# sht21-breakout_v2.net
KiCad netlist of a schematic drawn in EAGLE
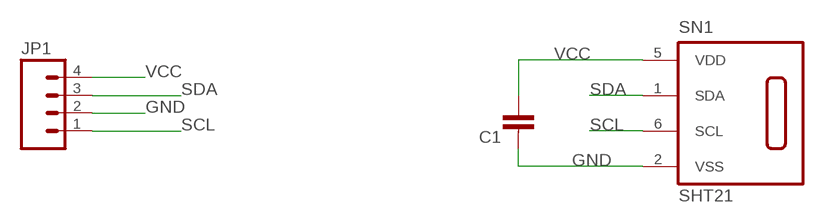
[diagram p0: schematic, sheet 1]

(export (version "E")
  (design (tool "Eeschema 10.0.6"))
  (components
    (comp (ref "C1")
      (value "CAPACITOR0603-N")
      (footprint "eagle-import:C0603-N")
      (libsource (lib "eagle-import") (part "CAPACITOR0603-N"))
    )
    (comp (ref "JP1")
      (value "M04LONGPADS")
      (footprint "eagle-import:1X04_LONGPADS")
      (libsource (lib "eagle-import") (part "M04LONGPADS"))
    )
    (comp (ref "SN1")
      (value "SHT21")
      (footprint "eagle-import:DFN6_SHT")
      (libsource (lib "eagle-import") (part "SHT21"))
    )
  )
  (nets
    (net (code "1") (name "/GND") (class "Default")
      (node (ref "C1") (pin "1") (pinfunction "1_1") (pintype "passive"))
      (node (ref "JP1") (pin "2") (pinfunction "2_2") (pintype "passive"))
      (node (ref "SN1") (pin "2") (pinfunction "VSS_2") (pintype "power_in"))
    )
    (net (code "2") (name "/SCL") (class "Default")
      (node (ref "JP1") (pin "1") (pinfunction "1_1") (pintype "passive"))
      (node (ref "SN1") (pin "6") (pinfunction "SCL_6") (pintype "bidirectional"))
    )
    (net (code "3") (name "/SDA") (class "Default")
      (node (ref "JP1") (pin "3") (pinfunction "3_3") (pintype "passive"))
      (node (ref "SN1") (pin "1") (pinfunction "SDA_1") (pintype "bidirectional"))
    )
    (net (code "4") (name "/VCC") (class "Default")
      (node (ref "C1") (pin "2") (pinfunction "2_2") (pintype "passive"))
      (node (ref "JP1") (pin "4") (pinfunction "4_4") (pintype "passive"))
      (node (ref "SN1") (pin "5") (pinfunction "VDD_5") (pintype "power_in"))
    )
  )
)
